# Sheet1.net
KiCad netlist of a schematic drawn in Altium Designer
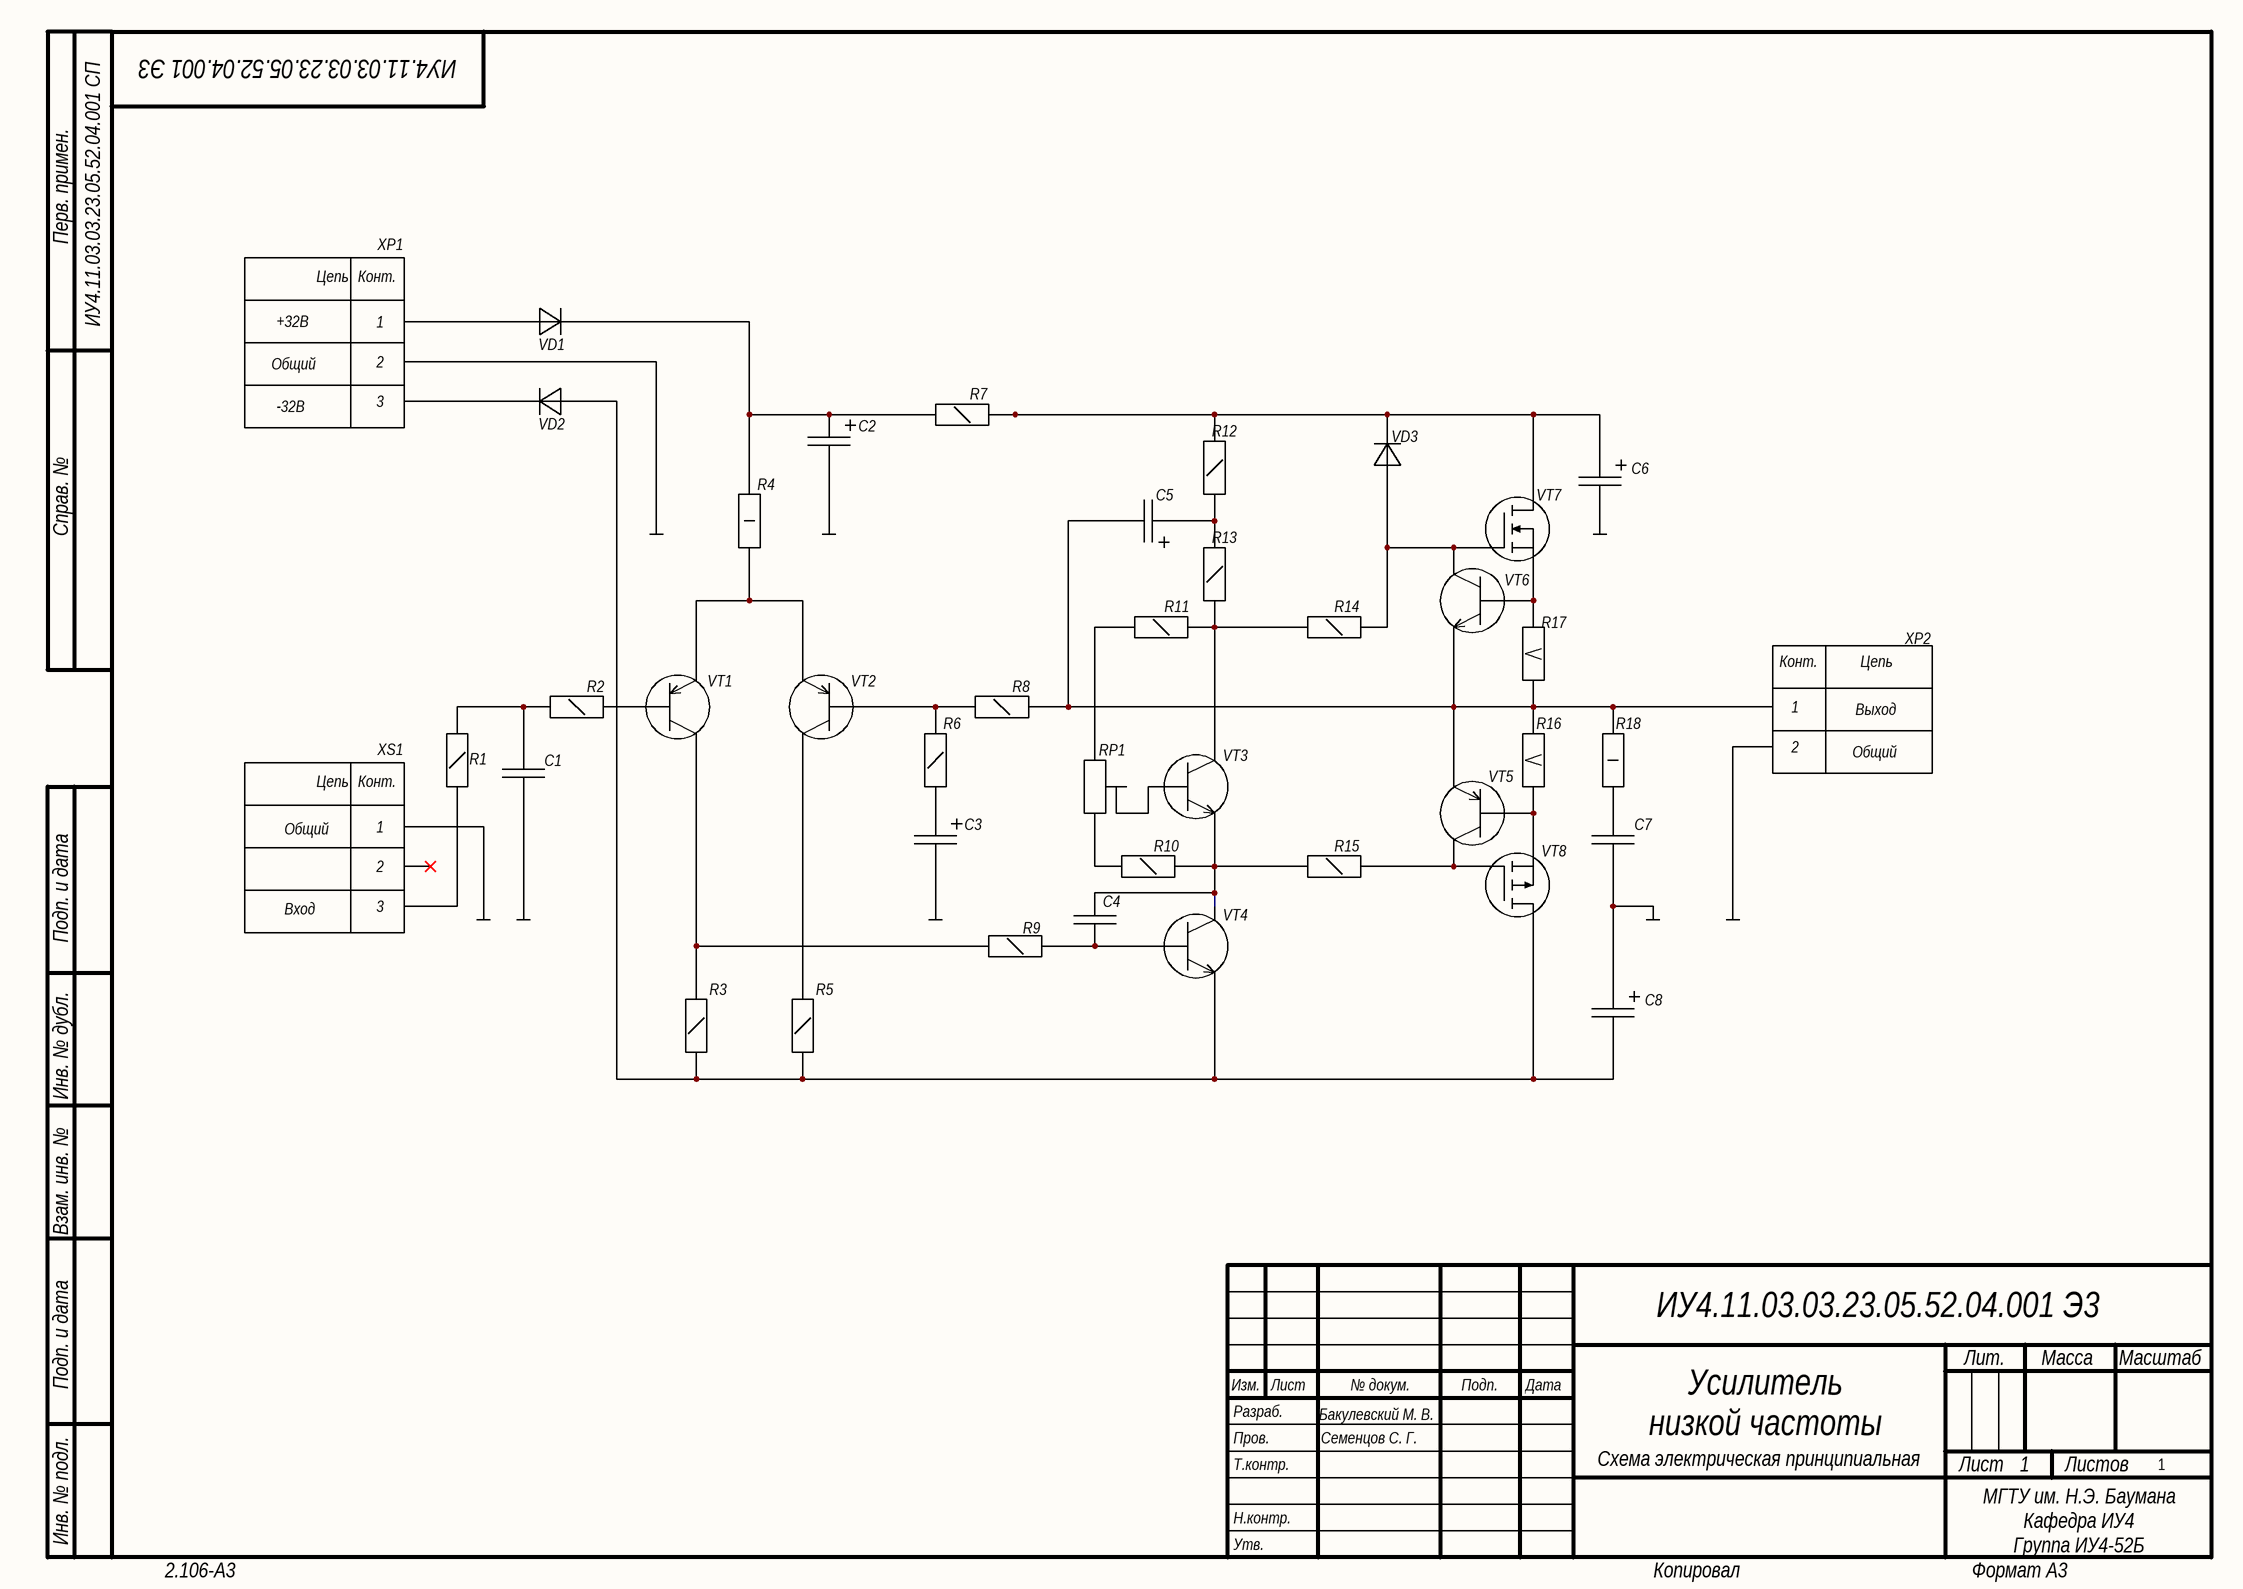
[diagram p0: Sheet1.SchDoc]

(export (version "E")
  (design (tool "Eeschema 10.0.6"))
  (components
    (comp (ref "C1")
      (value "Cap Ceramic 100pF")
      (footprint "CAPRR508-350X500X500")
      (libsource (lib "Schlib1") (part "Cap Ceramic 100pF"))
    )
    (comp (ref "C2")
      (value "2200uF 35V")
      (footprint "CAPPR350-800X700")
      (libsource (lib "Schlib1") (part "Cap Polarity 47uF 50V"))
    )
    (comp (ref "C3")
      (value "100uF 100V")
      (footprint "CAPPR500-1000X2050")
      (libsource (lib "Schlib1") (part "Cap Polarity 100uF 100V"))
    )
    (comp (ref "C4")
      (value "Cap Ceramic 100pF")
      (footprint "CAPRR508-350X500X500")
      (libsource (lib "Schlib1") (part "Cap Ceramic 100pF"))
    )
    (comp (ref "C5")
      (value "2200uF 35V")
      (footprint "CAPPR350-800X700")
      (libsource (lib "Schlib1") (part "Cap Polarity 47uF 50V"))
    )
    (comp (ref "C6")
      (value "2200uF 35V")
      (footprint "CAPPR750-1600X3150")
      (libsource (lib "Schlib1") (part "Cap Polarity 2200uF 35V"))
    )
    (comp (ref "C7")
      (value "2200uF 35V")
      (footprint "CAPR1000-400X1300X950")
      (libsource (lib "Schlib1") (part "Cap Film 0.68uF 250V"))
    )
    (comp (ref "C8")
      (value "2200uF 35V")
      (footprint "CAPPR750-1600X3150")
      (libsource (lib "Schlib1") (part "Cap Polarity 2200uF 35V"))
    )
    (comp (ref "R1")
      (value "Resistor 0.25W")
      (footprint "RES1016-630X250")
      (libsource (lib "Schlib1") (part "Resistor 0.25W"))
    )
    (comp (ref "R2")
      (value "Resistor 0.25W")
      (footprint "RES1016-630X250")
      (libsource (lib "Schlib1") (part "Resistor 0.25W"))
    )
    (comp (ref "R3")
      (value "Resistor 0.25W")
      (footprint "RES1016-630X250")
      (libsource (lib "Schlib1") (part "Resistor 0.25W"))
    )
    (comp (ref "R4")
      (value "Resistor 1W")
      (footprint "RES1651-1000X390")
      (libsource (lib "Schlib1") (part "Resistor 1W"))
    )
    (comp (ref "R5")
      (value "Resistor 0.25W")
      (footprint "RES1016-630X250")
      (libsource (lib "Schlib1") (part "Resistor 0.25W"))
    )
    (comp (ref "R6")
      (value "Resistor 0.25W")
      (footprint "RES1016-630X250")
      (libsource (lib "Schlib1") (part "Resistor 0.25W"))
    )
    (comp (ref "R7")
      (value "Resistor 0.25W")
      (footprint "RES1016-630X250")
      (libsource (lib "Schlib1") (part "Resistor 0.25W"))
    )
    (comp (ref "R8")
      (value "Resistor 0.25W")
      (footprint "RES1016-630X250")
      (libsource (lib "Schlib1") (part "Resistor 0.25W"))
    )
    (comp (ref "R9")
      (value "Resistor 0.25W")
      (footprint "RES1016-630X250")
      (libsource (lib "Schlib1") (part "Resistor 0.25W"))
    )
    (comp (ref "R10")
      (value "Resistor 0.25W")
      (footprint "RES1016-630X250")
      (libsource (lib "Schlib1") (part "Resistor 0.25W"))
    )
    (comp (ref "R11")
      (value "Resistor 0.25W")
      (footprint "RES1016-630X250")
      (libsource (lib "Schlib1") (part "Resistor 0.25W"))
    )
    (comp (ref "R12")
      (value "Resistor 0.25W")
      (footprint "RES1016-630X250")
      (libsource (lib "Schlib1") (part "Resistor 0.25W"))
    )
    (comp (ref "R13")
      (value "Resistor 0.25W")
      (footprint "RES1016-630X250")
      (libsource (lib "Schlib1") (part "Resistor 0.25W"))
    )
    (comp (ref "R14")
      (value "Resistor 0.25W")
      (footprint "RES1016-630X250")
      (libsource (lib "Schlib1") (part "Resistor 0.25W"))
    )
    (comp (ref "R15")
      (value "Resistor 0.25W")
      (footprint "RES1016-630X250")
      (libsource (lib "Schlib1") (part "Resistor 0.25W"))
    )
    (comp (ref "R16")
      (value "Resistor 5W")
      (footprint "RES_5W")
      (libsource (lib "Schlib1") (part "Resistor 5W"))
    )
    (comp (ref "R17")
      (value "Resistor 5W")
      (footprint "RES_5W")
      (libsource (lib "Schlib1") (part "Resistor 5W"))
    )
    (comp (ref "R18")
      (value "Resistor 1W")
      (footprint "RES1651-1000X390")
      (libsource (lib "Schlib1") (part "Resistor 1W"))
    )
    (comp (ref "RP1")
      (value "~")
      (footprint "TRIM_BOURNS_3296W")
      (fields
        (field (name "MANUFACTURER") "Bourns")
        (field (name "PARTNUMBER") "3296W-1-103LF")
        (field (name "VALUEMANUFACTURERPARTNUMBER") "Resistor film, , , 3296W, 0.5W, -55...+125°C")
      )
      (libsource (lib "Schlib1") (part "Resistor Trimmer 1K"))
    )
    (comp (ref "VD1")
      (value "Diode 15SQ045")
      (footprint "R6")
      (fields (field (name "PUBLISHER") "Andrew Danich"))
      (libsource (lib "Schlib1") (part "Diode 15SQ045"))
    )
    (comp (ref "VD2")
      (value "Diode 15SQ045")
      (footprint "R6")
      (fields (field (name "PUBLISHER") "Andrew Danich"))
      (libsource (lib "Schlib1") (part "Diode 15SQ045"))
    )
    (comp (ref "VD3")
      (value "Diode 1N4002")
      (footprint "DO-41")
      (fields (field (name "PUBLISHER") "Andrew Danich"))
      (libsource (lib "Schlib1") (part "Diode 1N4002"))
    )
    (comp (ref "VT1") (value "BC556B") (footprint "TO-92-A") (libsource (lib "Schlib1") (part "BC556B")))
    (comp (ref "VT2") (value "BC556B") (footprint "TO-92-A") (libsource (lib "Schlib1") (part "BC556B")))
    (comp (ref "VT3")
      (value "Transistor NPN BC546C")
      (footprint "TO-92-A")
      (libsource (lib "Schlib1") (part "Transistor NPN BC546C"))
    )
    (comp (ref "VT4")
      (value "Transistor NPN BC546C")
      (footprint "TO-92-A")
      (libsource (lib "Schlib1") (part "Transistor NPN BC546C"))
    )
    (comp (ref "VT5") (value "BC556B") (footprint "TO-92-A") (libsource (lib "Schlib1") (part "BC556B")))
    (comp (ref "VT6") (value "BC546C") (footprint "TO-92-A") (libsource (lib "Schlib1") (part "BC546C")))
    (comp (ref "VT7") (value "~") (footprint "TO-220AB") (libsource (lib "Schlib1") (part "IRF510PBF")))
    (comp (ref "VT8")
      (value "IRF9510PBF")
      (footprint "TO-220AB")
      (libsource (lib "Schlib1") (part "IRF9510PBF"))
    )
    (comp (ref "XP1")
      (value "Общий")
      (footprint "15EDGRC-3.81-03P")
      (libsource (lib "Schlib1") (part "Connector Power 3 pin"))
    )
    (comp (ref "XP2")
      (value "Connector Dynamic 2 pin")
      (footprint "15EDGRC-3.81-02P")
      (libsource (lib "Schlib1") (part "Connector Dynamic 2 pin"))
    )
    (comp (ref "XS1")
      (value "Общий")
      (footprint "ST-025")
      (libsource (lib "Schlib1") (part "Connector Audio 3 pin"))
    )
  )
  (nets
    (net (code "1") (name "GND") (class "Default")
      (node (ref "C1") (pin "2") (pinfunction "2_2") (pintype "passive"))
      (node (ref "C2") (pin "2") (pinfunction "2_2") (pintype "passive"))
      (node (ref "C3") (pin "2") (pinfunction "2_2") (pintype "passive"))
      (node (ref "C6") (pin "2") (pinfunction "2_2") (pintype "passive"))
      (node (ref "C7") (pin "2") (pinfunction "2_2") (pintype "passive"))
      (node (ref "C8") (pin "1") (pinfunction "1_1") (pintype "passive"))
      (node (ref "XP1") (pin "2") (pinfunction "2_2") (pintype "passive"))
      (node (ref "XP2") (pin "2") (pinfunction "2_2") (pintype "passive"))
      (node (ref "XS1") (pin "1") (pinfunction "1_1") (pintype "passive"))
    )
    (net (code "2") (name "Net-(C1-Pad1)") (class "Default")
      (node (ref "C1") (pin "1") (pinfunction "1_1") (pintype "passive"))
      (node (ref "R1") (pin "1") (pinfunction "1_1") (pintype "passive"))
      (node (ref "R2") (pin "1") (pinfunction "1_1") (pintype "passive"))
    )
    (net (code "3") (name "Net-(C3-Pad1)") (class "Default")
      (node (ref "C3") (pin "1") (pinfunction "1_1") (pintype "passive"))
      (node (ref "R6") (pin "2") (pinfunction "2_2") (pintype "passive"))
    )
    (net (code "4") (name "Net-(C5-Pad1)") (class "Default")
      (node (ref "C5") (pin "1") (pinfunction "1_1") (pintype "passive"))
      (node (ref "R12") (pin "1") (pinfunction "1_1") (pintype "passive"))
      (node (ref "R13") (pin "2") (pinfunction "2_2") (pintype "passive"))
    )
    (net (code "5") (name "Net-(C7-Pad1)") (class "Default")
      (node (ref "C7") (pin "1") (pinfunction "1_1") (pintype "passive"))
      (node (ref "R18") (pin "1") (pinfunction "1_1") (pintype "passive"))
    )
    (net (code "6") (name "Net-(R1-Pad2)") (class "Default")
      (node (ref "R1") (pin "2") (pinfunction "2_2") (pintype "passive"))
      (node (ref "XS1") (pin "3") (pinfunction "3_3") (pintype "passive"))
    )
    (net (code "7") (name "Net-(R10-Pad2)") (class "Default")
      (node (ref "R10") (pin "2") (pinfunction "2_2") (pintype "passive"))
      (node (ref "RP1") (pin "3") (pinfunction "3_3") (pintype "passive"))
    )
    (net (code "8") (name "Net-(R11-Pad1)") (class "Default")
      (node (ref "R11") (pin "1") (pinfunction "1_1") (pintype "passive"))
      (node (ref "RP1") (pin "1") (pinfunction "1_1") (pintype "passive"))
    )
    (net (code "9") (name "Net-(VD1-А)") (class "Default")
      (node (ref "VD1") (pin "1") (pinfunction "А_1") (pintype "passive"))
      (node (ref "XP1") (pin "1") (pinfunction "1_1") (pintype "passive"))
    )
    (net (code "10") (name "Net-(VD1-К)") (class "Default")
      (node (ref "C2") (pin "1") (pinfunction "1_1") (pintype "passive"))
      (node (ref "R4") (pin "1") (pinfunction "1_1") (pintype "passive"))
      (node (ref "R7") (pin "1") (pinfunction "1_1") (pintype "passive"))
      (node (ref "VD1") (pin "2") (pinfunction "К_2") (pintype "passive"))
    )
    (net (code "11") (name "Net-(VD2-А)") (class "Default")
      (node (ref "C8") (pin "2") (pinfunction "2_2") (pintype "passive"))
      (node (ref "R3") (pin "1") (pinfunction "1_1") (pintype "passive"))
      (node (ref "R5") (pin "1") (pinfunction "1_1") (pintype "passive"))
      (node (ref "VD2") (pin "1") (pinfunction "А_1") (pintype "passive"))
      (node (ref "VT4") (pin "3") (pinfunction "Э_3") (pintype "passive"))
      (node (ref "VT8") (pin "2") (pinfunction "D_2") (pintype "passive"))
    )
    (net (code "12") (name "Net-(VD2-К)") (class "Default")
      (node (ref "VD2") (pin "2") (pinfunction "К_2") (pintype "passive"))
      (node (ref "XP1") (pin "3") (pinfunction "3_3") (pintype "passive"))
    )
    (net (code "13") (name "Net-(VD3-А)") (class "Default")
      (node (ref "R14") (pin "2") (pinfunction "2_2") (pintype "passive"))
      (node (ref "VD3") (pin "1") (pinfunction "А_1") (pintype "passive"))
      (node (ref "VT6") (pin "1") (pinfunction "К_1") (pintype "passive"))
      (node (ref "VT7") (pin "1") (pinfunction "G_1") (pintype "passive"))
    )
    (net (code "14") (name "Net-(VD3-К)") (class "Default")
      (node (ref "C6") (pin "1") (pinfunction "1_1") (pintype "passive"))
      (node (ref "R12") (pin "2") (pinfunction "2_2") (pintype "passive"))
      (node (ref "R7") (pin "2") (pinfunction "2_2") (pintype "passive"))
      (node (ref "VD3") (pin "2") (pinfunction "К_2") (pintype "passive"))
      (node (ref "VT7") (pin "2") (pinfunction "D_2") (pintype "passive"))
    )
    (net (code "15") (name "Net-(VT1-Б)") (class "Default")
      (node (ref "R2") (pin "2") (pinfunction "2_2") (pintype "passive"))
      (node (ref "VT1") (pin "2") (pinfunction "Б_2") (pintype "passive"))
    )
    (net (code "16") (name "Net-(VT1-К)") (class "Default")
      (node (ref "R3") (pin "2") (pinfunction "2_2") (pintype "passive"))
      (node (ref "R9") (pin "2") (pinfunction "2_2") (pintype "passive"))
      (node (ref "VT1") (pin "1") (pinfunction "К_1") (pintype "passive"))
    )
    (net (code "17") (name "Net-(VT1-Э)") (class "Default")
      (node (ref "R4") (pin "2") (pinfunction "2_2") (pintype "passive"))
      (node (ref "VT1") (pin "3") (pinfunction "Э_3") (pintype "passive"))
      (node (ref "VT2") (pin "3") (pinfunction "Э_3") (pintype "passive"))
    )
    (net (code "18") (name "Net-(VT2-Б)") (class "Default")
      (node (ref "R6") (pin "1") (pinfunction "1_1") (pintype "passive"))
      (node (ref "R8") (pin "1") (pinfunction "1_1") (pintype "passive"))
      (node (ref "VT2") (pin "2") (pinfunction "Б_2") (pintype "passive"))
    )
    (net (code "19") (name "Net-(VT2-К)") (class "Default")
      (node (ref "R5") (pin "2") (pinfunction "2_2") (pintype "passive"))
      (node (ref "VT2") (pin "1") (pinfunction "К_1") (pintype "passive"))
    )
    (net (code "20") (name "Net-(VT3-Б)") (class "Default")
      (node (ref "RP1") (pin "2") (pinfunction "2_2") (pintype "passive"))
      (node (ref "VT3") (pin "2") (pinfunction "Б_2") (pintype "passive"))
    )
    (net (code "21") (name "Net-(VT3-К)") (class "Default")
      (node (ref "R11") (pin "2") (pinfunction "2_2") (pintype "passive"))
      (node (ref "R13") (pin "1") (pinfunction "1_1") (pintype "passive"))
      (node (ref "R14") (pin "1") (pinfunction "1_1") (pintype "passive"))
      (node (ref "VT3") (pin "1") (pinfunction "К_1") (pintype "passive"))
    )
    (net (code "22") (name "Net-(VT3-Э)") (class "Default")
      (node (ref "C4") (pin "2") (pinfunction "2_2") (pintype "passive"))
      (node (ref "R10") (pin "1") (pinfunction "1_1") (pintype "passive"))
      (node (ref "R15") (pin "1") (pinfunction "1_1") (pintype "passive"))
      (node (ref "VT3") (pin "3") (pinfunction "Э_3") (pintype "passive"))
      (node (ref "VT4") (pin "1") (pinfunction "К_1") (pintype "passive"))
    )
    (net (code "23") (name "Net-(VT4-Б)") (class "Default")
      (node (ref "C4") (pin "1") (pinfunction "1_1") (pintype "passive"))
      (node (ref "R9") (pin "1") (pinfunction "1_1") (pintype "passive"))
      (node (ref "VT4") (pin "2") (pinfunction "Б_2") (pintype "passive"))
    )
    (net (code "24") (name "Net-(VT5-Б)") (class "Default")
      (node (ref "R16") (pin "1") (pinfunction "1_1") (pintype "passive"))
      (node (ref "VT5") (pin "2") (pinfunction "Б_2") (pintype "passive"))
      (node (ref "VT8") (pin "3") (pinfunction "S_3") (pintype "passive"))
    )
    (net (code "25") (name "Net-(VT5-К)") (class "Default")
      (node (ref "R15") (pin "2") (pinfunction "2_2") (pintype "passive"))
      (node (ref "VT5") (pin "1") (pinfunction "К_1") (pintype "passive"))
      (node (ref "VT8") (pin "1") (pinfunction "G_1") (pintype "passive"))
    )
    (net (code "26") (name "Net-(VT5-Э)") (class "Default")
      (node (ref "C5") (pin "2") (pinfunction "2_2") (pintype "passive"))
      (node (ref "R16") (pin "2") (pinfunction "2_2") (pintype "passive"))
      (node (ref "R17") (pin "1") (pinfunction "1_1") (pintype "passive"))
      (node (ref "R18") (pin "2") (pinfunction "2_2") (pintype "passive"))
      (node (ref "R8") (pin "2") (pinfunction "2_2") (pintype "passive"))
      (node (ref "VT5") (pin "3") (pinfunction "Э_3") (pintype "passive"))
      (node (ref "VT6") (pin "3") (pinfunction "Э_3") (pintype "passive"))
      (node (ref "XP2") (pin "1") (pinfunction "1_1") (pintype "passive"))
    )
    (net (code "27") (name "Net-(VT6-Б)") (class "Default")
      (node (ref "R17") (pin "2") (pinfunction "2_2") (pintype "passive"))
      (node (ref "VT6") (pin "2") (pinfunction "Б_2") (pintype "passive"))
      (node (ref "VT7") (pin "3") (pinfunction "S_3") (pintype "passive"))
    )
    (net (code "28") (name "unconnected-(XS1-Pad2)") (class "Default")
      (node (ref "XS1") (pin "2") (pinfunction "2_2") (pintype "passive+no_connect"))
    )
  )
)
